# PCB.net
KiCad netlist of a schematic drawn in EAGLE
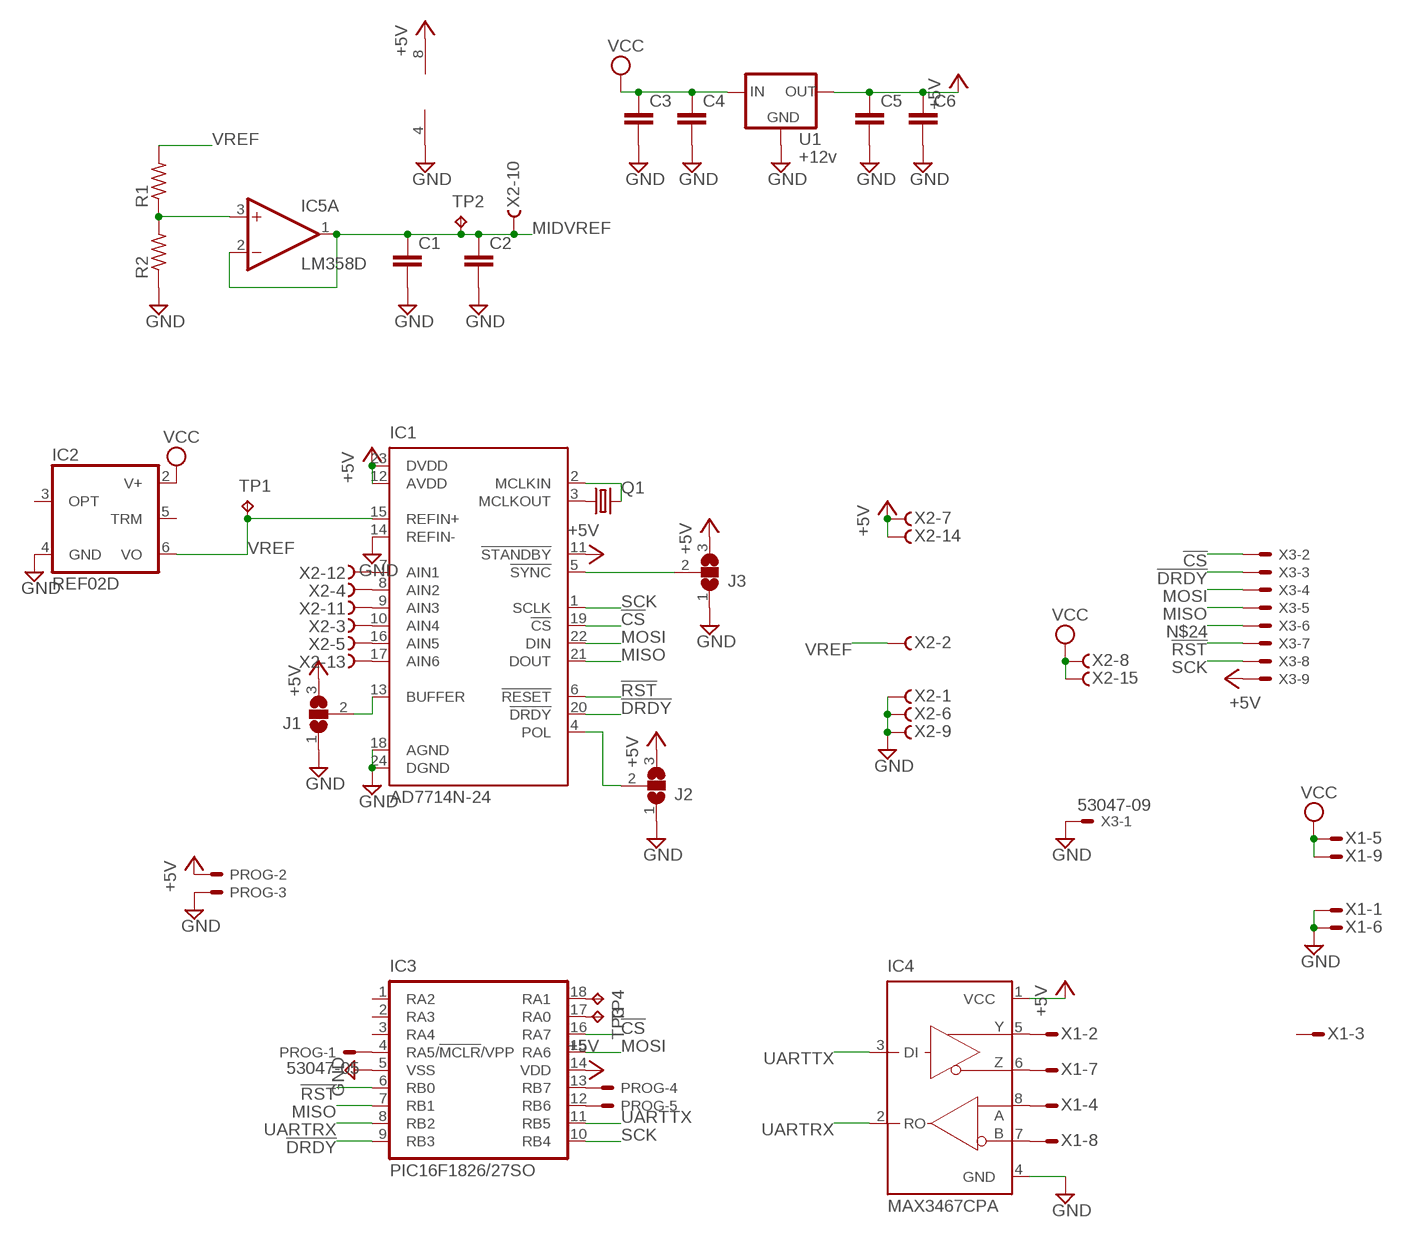
[diagram p0: schematic, sheet 1]

(export (version "E")
  (design (tool "Eeschema 10.0.6"))
  (components
    (comp (ref "C1")
      (value "C-EUC1206K")
      (footprint "eagle-import:C1206K")
      (libsource (lib "eagle-import") (part "C-EUC1206K"))
    )
    (comp (ref "C2")
      (value "C-EUC1206K")
      (footprint "eagle-import:C1206K")
      (libsource (lib "eagle-import") (part "C-EUC1206K"))
    )
    (comp (ref "C3")
      (value "C-EUC1206K")
      (footprint "eagle-import:C1206K")
      (libsource (lib "eagle-import") (part "C-EUC1206K"))
    )
    (comp (ref "C4")
      (value "C-EUC1206K")
      (footprint "eagle-import:C1206K")
      (libsource (lib "eagle-import") (part "C-EUC1206K"))
    )
    (comp (ref "C5")
      (value "C-EUC1206K")
      (footprint "eagle-import:C1206K")
      (libsource (lib "eagle-import") (part "C-EUC1206K"))
    )
    (comp (ref "C6")
      (value "C-EUC1206K")
      (footprint "eagle-import:C1206K")
      (libsource (lib "eagle-import") (part "C-EUC1206K"))
    )
    (comp (ref "IC1")
      (value "AD7714N-24")
      (footprint "eagle-import:DIL24-3")
      (fields (field (name "MF") "ALTERA CORPORATION") (field (name "MPN") "AD7714AN-5"))
      (libsource (lib "eagle-import") (part "AD7714N-24"))
    )
    (comp (ref "IC2")
      (value "REF02D")
      (footprint "eagle-import:SO08")
      (libsource (lib "eagle-import") (part "REF02D"))
    )
    (comp (ref "IC3")
      (value "PIC16F1826/27SO")
      (footprint "eagle-import:SO-18W")
      (libsource (lib "eagle-import") (part "PIC16F1826/27SO"))
    )
    (comp (ref "IC4")
      (value "MAX3467CPA")
      (footprint "eagle-import:SO08")
      (libsource (lib "eagle-import") (part "MAX3467PAC"))
    )
    (comp (ref "IC5")
      (value "LM358D")
      (footprint "eagle-import:SO08")
      (libsource (lib "eagle-import") (part "LM358D"))
    )
    (comp (ref "J1")
      (value "SJ2W")
      (footprint "eagle-import:SJ_2")
      (libsource (lib "eagle-import") (part "SJ2W"))
    )
    (comp (ref "J2")
      (value "SJ2W")
      (footprint "eagle-import:SJ_2")
      (libsource (lib "eagle-import") (part "SJ2W"))
    )
    (comp (ref "J3")
      (value "SJ2W")
      (footprint "eagle-import:SJ_2")
      (libsource (lib "eagle-import") (part "SJ2W"))
    )
    (comp (ref "PROG")
      (value "53047-05")
      (footprint "eagle-import:53047-05")
      (fields (field (name "MF") "MOLEX") (field (name "MPN") "53047-0510"))
      (libsource (lib "eagle-import") (part "53?-05047"))
    )
    (comp (ref "Q1")
      (value "CRYSTALHC49S")
      (footprint "eagle-import:HC49_S")
      (libsource (lib "eagle-import") (part "CRYSTALHC49S"))
    )
    (comp (ref "R1")
      (value "R-US_M1206")
      (footprint "eagle-import:M1206")
      (libsource (lib "eagle-import") (part "R-US_M1206"))
    )
    (comp (ref "R2")
      (value "R-US_M1206")
      (footprint "eagle-import:M1206")
      (libsource (lib "eagle-import") (part "R-US_M1206"))
    )
    (comp (ref "TP1")
      (value "TPB1,27")
      (footprint "eagle-import:B1,27")
      (libsource (lib "eagle-import") (part "TPB1,27"))
    )
    (comp (ref "TP2")
      (value "TPB1,27")
      (footprint "eagle-import:B1,27")
      (libsource (lib "eagle-import") (part "TPB1,27"))
    )
    (comp (ref "TP3")
      (value "TPB1,27")
      (footprint "eagle-import:B1,27")
      (libsource (lib "eagle-import") (part "TPB1,27"))
    )
    (comp (ref "TP4")
      (value "TPB1,27")
      (footprint "eagle-import:B1,27")
      (libsource (lib "eagle-import") (part "TPB1,27"))
    )
    (comp (ref "U1")
      (value "+12v")
      (footprint "eagle-import:TO-252")
      (libsource (lib "eagle-import") (part "V_REG_78XX7812"))
    )
    (comp (ref "X1")
      (value "M09HPS")
      (footprint "eagle-import:M09HP")
      (libsource (lib "eagle-import") (part "M09?SHP"))
    )
    (comp (ref "X2")
      (value "F15HPS")
      (footprint "eagle-import:F15HP")
      (libsource (lib "eagle-import") (part "F15?SHP"))
    )
    (comp (ref "X3")
      (value "53047-09")
      (footprint "eagle-import:53047-09")
      (fields (field (name "MPN") "53047-0910"))
      (libsource (lib "eagle-import") (part "53?-09047"))
    )
  )
  (nets
    (net (code "1") (name "+5V") (class "Default")
      (node (ref "C5") (pin "1") (pinfunction "1_1") (pintype "passive"))
      (node (ref "C6") (pin "1") (pinfunction "1_1") (pintype "passive"))
      (node (ref "IC1") (pin "11") (pinfunction "~{STANDBY}_11") (pintype "input"))
      (node (ref "IC1") (pin "12") (pinfunction "AVDD_12") (pintype "input"))
      (node (ref "IC1") (pin "23") (pinfunction "DVDD_23") (pintype "input"))
      (node (ref "IC3") (pin "14") (pinfunction "VDD_14") (pintype "power_in"))
      (node (ref "IC4") (pin "1") (pinfunction "VCC_1") (pintype "power_in"))
      (node (ref "IC5") (pin "8") (pinfunction "V+_8") (pintype "power_in"))
      (node (ref "J1") (pin "3") (pinfunction "3_3") (pintype "passive"))
      (node (ref "J2") (pin "3") (pinfunction "3_3") (pintype "passive"))
      (node (ref "J3") (pin "3") (pinfunction "3_3") (pintype "passive"))
      (node (ref "PROG") (pin "2") (pinfunction "S_2") (pintype "passive"))
      (node (ref "U1") (pin "2") (pinfunction "OUT_2") (pintype "passive"))
      (node (ref "X2") (pin "14") (pinfunction "F_14") (pintype "passive"))
      (node (ref "X2") (pin "7") (pinfunction "F_7") (pintype "passive"))
      (node (ref "X3") (pin "9") (pinfunction "S_9") (pintype "passive"))
    )
    (net (code "2") (name "/MIDVREF") (class "Default")
      (node (ref "C1") (pin "1") (pinfunction "1_1") (pintype "passive"))
      (node (ref "C2") (pin "1") (pinfunction "1_1") (pintype "passive"))
      (node (ref "IC5") (pin "1") (pinfunction "OUT_1") (pintype "output"))
      (node (ref "IC5") (pin "2") (pinfunction "-IN_2") (pintype "input"))
      (node (ref "TP2") (pin "TP") (pinfunction "TP_TP") (pintype "input"))
      (node (ref "X2") (pin "10") (pinfunction "F_10") (pintype "passive"))
    )
    (net (code "3") (name "/MISO") (class "Default")
      (node (ref "IC1") (pin "21") (pinfunction "DOUT_21") (pintype "output"))
      (node (ref "IC3") (pin "7") (pinfunction "RB1_7") (pintype "bidirectional"))
      (node (ref "X3") (pin "5") (pinfunction "S_5") (pintype "passive"))
    )
    (net (code "4") (name "/MOSI") (class "Default")
      (node (ref "IC1") (pin "22") (pinfunction "DIN_22") (pintype "input"))
      (node (ref "IC3") (pin "15") (pinfunction "RA6_15") (pintype "bidirectional"))
      (node (ref "X3") (pin "4") (pinfunction "S_4") (pintype "passive"))
    )
    (net (code "5") (name "/N$24") (class "Default")
      (node (ref "X3") (pin "6") (pinfunction "S_6") (pintype "passive"))
    )
    (net (code "6") (name "/SCK") (class "Default")
      (node (ref "IC1") (pin "1") (pinfunction "SCLK_1") (pintype "input"))
      (node (ref "IC3") (pin "10") (pinfunction "RB4_10") (pintype "bidirectional"))
      (node (ref "X3") (pin "8") (pinfunction "S_8") (pintype "passive"))
    )
    (net (code "7") (name "/UARTRX") (class "Default")
      (node (ref "IC3") (pin "8") (pinfunction "RB2_8") (pintype "bidirectional"))
      (node (ref "IC4") (pin "2") (pinfunction "RO_2") (pintype "output"))
    )
    (net (code "8") (name "/UARTTX") (class "Default")
      (node (ref "IC3") (pin "11") (pinfunction "RB5_11") (pintype "bidirectional"))
      (node (ref "IC4") (pin "3") (pinfunction "DI_3") (pintype "input"))
    )
    (net (code "9") (name "/VREF") (class "Default")
      (node (ref "IC1") (pin "15") (pinfunction "REFIN+_15") (pintype "input"))
      (node (ref "IC2") (pin "6") (pinfunction "VO_6") (pintype "output"))
      (node (ref "R1") (pin "2") (pinfunction "2_2") (pintype "passive"))
      (node (ref "TP1") (pin "TP") (pinfunction "TP_TP") (pintype "input"))
      (node (ref "X2") (pin "2") (pinfunction "F_2") (pintype "passive"))
    )
    (net (code "10") (name "/~{CS}") (class "Default")
      (node (ref "IC1") (pin "19") (pinfunction "~{CS}_19") (pintype "input"))
      (node (ref "IC3") (pin "16") (pinfunction "RA7_16") (pintype "bidirectional"))
      (node (ref "X3") (pin "2") (pinfunction "S_2") (pintype "passive"))
    )
    (net (code "11") (name "/~{DRDY}") (class "Default")
      (node (ref "IC1") (pin "20") (pinfunction "~{DRDY}_20") (pintype "input"))
      (node (ref "IC3") (pin "9") (pinfunction "RB3_9") (pintype "bidirectional"))
      (node (ref "X3") (pin "3") (pinfunction "S_3") (pintype "passive"))
    )
    (net (code "12") (name "/~{RST}") (class "Default")
      (node (ref "IC1") (pin "6") (pinfunction "~{RESET}_6") (pintype "input"))
      (node (ref "IC3") (pin "6") (pinfunction "RB0_6") (pintype "bidirectional"))
      (node (ref "X3") (pin "7") (pinfunction "S_7") (pintype "passive"))
    )
    (net (code "13") (name "GND") (class "Default")
      (node (ref "C1") (pin "2") (pinfunction "2_2") (pintype "passive"))
      (node (ref "C2") (pin "2") (pinfunction "2_2") (pintype "passive"))
      (node (ref "C3") (pin "2") (pinfunction "2_2") (pintype "passive"))
      (node (ref "C4") (pin "2") (pinfunction "2_2") (pintype "passive"))
      (node (ref "C5") (pin "2") (pinfunction "2_2") (pintype "passive"))
      (node (ref "C6") (pin "2") (pinfunction "2_2") (pintype "passive"))
      (node (ref "IC1") (pin "14") (pinfunction "REFIN-_14") (pintype "input"))
      (node (ref "IC1") (pin "18") (pinfunction "AGND_18") (pintype "input"))
      (node (ref "IC1") (pin "24") (pinfunction "DGND_24") (pintype "input"))
      (node (ref "IC2") (pin "4") (pinfunction "GND_4") (pintype "power_in"))
      (node (ref "IC3") (pin "5") (pinfunction "VSS_5") (pintype "power_in"))
      (node (ref "IC4") (pin "4") (pinfunction "GND_4") (pintype "power_in"))
      (node (ref "IC5") (pin "4") (pinfunction "V-_4") (pintype "power_in"))
      (node (ref "J1") (pin "1") (pinfunction "1_1") (pintype "passive"))
      (node (ref "J2") (pin "1") (pinfunction "1_1") (pintype "passive"))
      (node (ref "J3") (pin "1") (pinfunction "1_1") (pintype "passive"))
      (node (ref "PROG") (pin "3") (pinfunction "S_3") (pintype "passive"))
      (node (ref "R2") (pin "1") (pinfunction "1_1") (pintype "passive"))
      (node (ref "U1") (pin "3") (pinfunction "GND_3") (pintype "input"))
      (node (ref "X1") (pin "1") (pinfunction "M_1") (pintype "passive"))
      (node (ref "X1") (pin "6") (pinfunction "M_6") (pintype "passive"))
      (node (ref "X2") (pin "1") (pinfunction "F_1") (pintype "passive"))
      (node (ref "X2") (pin "6") (pinfunction "F_6") (pintype "passive"))
      (node (ref "X2") (pin "9") (pinfunction "F_9") (pintype "passive"))
      (node (ref "X3") (pin "1") (pinfunction "S_1") (pintype "passive"))
    )
    (net (code "14") (name "Net-(IC1-AIN1)") (class "Default")
      (node (ref "IC1") (pin "7") (pinfunction "AIN1_7") (pintype "input"))
      (node (ref "X2") (pin "12") (pinfunction "F_12") (pintype "passive"))
    )
    (net (code "15") (name "Net-(IC1-AIN2)") (class "Default")
      (node (ref "IC1") (pin "8") (pinfunction "AIN2_8") (pintype "input"))
      (node (ref "X2") (pin "4") (pinfunction "F_4") (pintype "passive"))
    )
    (net (code "16") (name "Net-(IC1-AIN3)") (class "Default")
      (node (ref "IC1") (pin "9") (pinfunction "AIN3_9") (pintype "input"))
      (node (ref "X2") (pin "11") (pinfunction "F_11") (pintype "passive"))
    )
    (net (code "17") (name "Net-(IC1-AIN4)") (class "Default")
      (node (ref "IC1") (pin "10") (pinfunction "AIN4_10") (pintype "input"))
      (node (ref "X2") (pin "3") (pinfunction "F_3") (pintype "passive"))
    )
    (net (code "18") (name "Net-(IC1-AIN5)") (class "Default")
      (node (ref "IC1") (pin "16") (pinfunction "AIN5_16") (pintype "input"))
      (node (ref "X2") (pin "5") (pinfunction "F_5") (pintype "passive"))
    )
    (net (code "19") (name "Net-(IC1-AIN6)") (class "Default")
      (node (ref "IC1") (pin "17") (pinfunction "AIN6_17") (pintype "input"))
      (node (ref "X2") (pin "13") (pinfunction "F_13") (pintype "passive"))
    )
    (net (code "20") (name "Net-(IC1-BUFFER)") (class "Default")
      (node (ref "IC1") (pin "13") (pinfunction "BUFFER_13") (pintype "input"))
      (node (ref "J1") (pin "2") (pinfunction "2_2") (pintype "passive"))
    )
    (net (code "21") (name "Net-(IC1-MCLKIN)") (class "Default")
      (node (ref "IC1") (pin "2") (pinfunction "MCLKIN_2") (pintype "input"))
      (node (ref "Q1") (pin "2") (pinfunction "2_2") (pintype "passive"))
    )
    (net (code "22") (name "Net-(IC1-MCLKOUT)") (class "Default")
      (node (ref "IC1") (pin "3") (pinfunction "MCLKOUT_3") (pintype "output"))
      (node (ref "Q1") (pin "1") (pinfunction "1_1") (pintype "passive"))
    )
    (net (code "23") (name "Net-(IC1-POL)") (class "Default")
      (node (ref "IC1") (pin "4") (pinfunction "POL_4") (pintype "input"))
      (node (ref "J2") (pin "2") (pinfunction "2_2") (pintype "passive"))
    )
    (net (code "24") (name "Net-(IC1-~{SYNC})") (class "Default")
      (node (ref "IC1") (pin "5") (pinfunction "~{SYNC}_5") (pintype "input"))
      (node (ref "J3") (pin "2") (pinfunction "2_2") (pintype "passive"))
    )
    (net (code "25") (name "Net-(IC3-RA0)") (class "Default")
      (node (ref "IC3") (pin "17") (pinfunction "RA0_17") (pintype "bidirectional"))
      (node (ref "TP3") (pin "TP") (pinfunction "TP_TP") (pintype "input"))
    )
    (net (code "26") (name "Net-(IC3-RA1)") (class "Default")
      (node (ref "IC3") (pin "18") (pinfunction "RA1_18") (pintype "bidirectional"))
      (node (ref "TP4") (pin "TP") (pinfunction "TP_TP") (pintype "input"))
    )
    (net (code "27") (name "Net-(IC3-RA5{slash}~{MCLR}{slash}VPP)") (class "Default")
      (node (ref "IC3") (pin "4") (pinfunction "RA5/~{MCLR}/VPP_4") (pintype "bidirectional"))
      (node (ref "PROG") (pin "1") (pinfunction "S_1") (pintype "passive"))
    )
    (net (code "28") (name "Net-(IC3-RB6)") (class "Default")
      (node (ref "IC3") (pin "12") (pinfunction "RB6_12") (pintype "bidirectional"))
      (node (ref "PROG") (pin "5") (pinfunction "S_5") (pintype "passive"))
    )
    (net (code "29") (name "Net-(IC3-RB7)") (class "Default")
      (node (ref "IC3") (pin "13") (pinfunction "RB7_13") (pintype "bidirectional"))
      (node (ref "PROG") (pin "4") (pinfunction "S_4") (pintype "passive"))
    )
    (net (code "30") (name "Net-(IC4-A)") (class "Default")
      (node (ref "IC4") (pin "8") (pinfunction "A_8") (pintype "passive"))
      (node (ref "X1") (pin "4") (pinfunction "M_4") (pintype "passive"))
    )
    (net (code "31") (name "Net-(IC4-B)") (class "Default")
      (node (ref "IC4") (pin "7") (pinfunction "B_7") (pintype "passive"))
      (node (ref "X1") (pin "8") (pinfunction "M_8") (pintype "passive"))
    )
    (net (code "32") (name "Net-(IC4-Y)") (class "Default")
      (node (ref "IC4") (pin "5") (pinfunction "Y_5") (pintype "passive"))
      (node (ref "X1") (pin "2") (pinfunction "M_2") (pintype "passive"))
    )
    (net (code "33") (name "Net-(IC4-Z)") (class "Default")
      (node (ref "IC4") (pin "6") (pinfunction "Z_6") (pintype "passive"))
      (node (ref "X1") (pin "7") (pinfunction "M_7") (pintype "passive"))
    )
    (net (code "34") (name "Net-(IC5A-+IN)") (class "Default")
      (node (ref "IC5") (pin "3") (pinfunction "+IN_3") (pintype "input"))
      (node (ref "R1") (pin "1") (pinfunction "1_1") (pintype "passive"))
      (node (ref "R2") (pin "2") (pinfunction "2_2") (pintype "passive"))
    )
    (net (code "35") (name "VCC") (class "Default")
      (node (ref "C3") (pin "1") (pinfunction "1_1") (pintype "passive"))
      (node (ref "C4") (pin "1") (pinfunction "1_1") (pintype "passive"))
      (node (ref "IC2") (pin "2") (pinfunction "V+_2") (pintype "power_in"))
      (node (ref "U1") (pin "1") (pinfunction "IN_1") (pintype "input"))
      (node (ref "X1") (pin "5") (pinfunction "M_5") (pintype "passive"))
      (node (ref "X1") (pin "9") (pinfunction "M_9") (pintype "passive"))
      (node (ref "X2") (pin "15") (pinfunction "F_15") (pintype "passive"))
      (node (ref "X2") (pin "8") (pinfunction "F_8") (pintype "passive"))
    )
    (net (code "36") (name "unconnected-(IC2-OPT-Pad3)") (class "Default")
      (node (ref "IC2") (pin "3") (pinfunction "OPT_3") (pintype "output"))
    )
    (net (code "37") (name "unconnected-(IC2-TRM-Pad5)") (class "Default")
      (node (ref "IC2") (pin "5") (pinfunction "TRM_5") (pintype "input"))
    )
    (net (code "38") (name "unconnected-(IC3-RA2-Pad1)") (class "Default")
      (node (ref "IC3") (pin "1") (pinfunction "RA2_1") (pintype "bidirectional"))
    )
    (net (code "39") (name "unconnected-(IC3-RA3-Pad2)") (class "Default")
      (node (ref "IC3") (pin "2") (pinfunction "RA3_2") (pintype "bidirectional"))
    )
    (net (code "40") (name "unconnected-(IC3-RA4-Pad3)") (class "Default")
      (node (ref "IC3") (pin "3") (pinfunction "RA4_3") (pintype "bidirectional"))
    )
    (net (code "41") (name "unconnected-(X1C-M-Pad3)") (class "Default")
      (node (ref "X1") (pin "3") (pinfunction "M_3") (pintype "passive"))
    )
  )
)
